# Bendy1.net
KiCad netlist of a schematic drawn in EAGLE
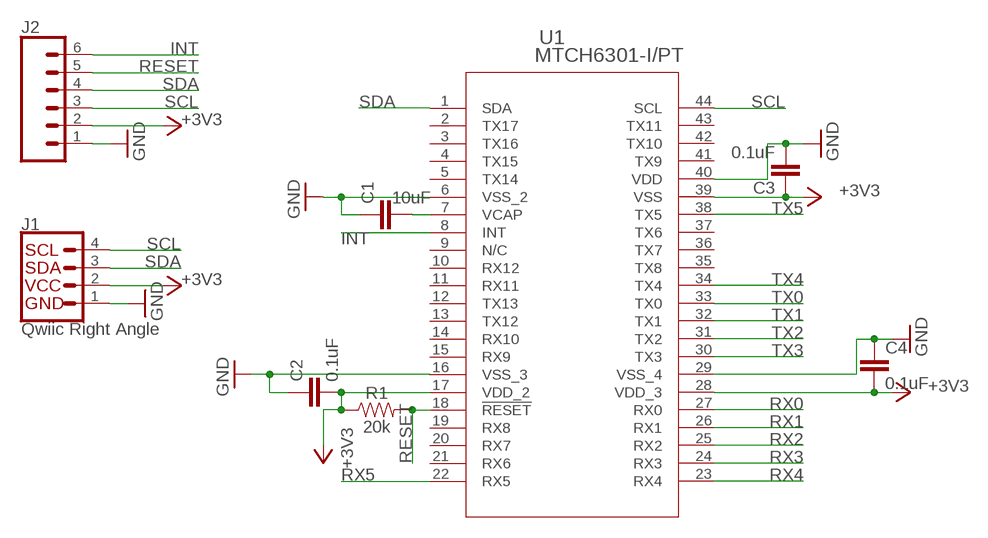
[diagram p0: schematic, sheet 1]

(export (version "E")
  (design (tool "Eeschema 10.0.6"))
  (components
    (comp (ref "C1")
      (value "10uF")
      (footprint "eagle-import:0603")
      (libsource (lib "eagle-import") (part "10UF-0603-6.3V-20%"))
    )
    (comp (ref "C2")
      (value "0.1uF")
      (footprint "eagle-import:0603")
      (libsource (lib "eagle-import") (part "0.1UF-0603-25V-(+80/-20%)"))
    )
    (comp (ref "C3")
      (value "0.1uF")
      (footprint "eagle-import:0603")
      (libsource (lib "eagle-import") (part "0.1UF-0603-25V-(+80/-20%)"))
    )
    (comp (ref "C4")
      (value "0.1uF")
      (footprint "eagle-import:0402")
      (libsource (lib "eagle-import") (part "0.1UF-0402-10V-10%-X7R"))
    )
    (comp (ref "J1")
      (value "Qwiic Right Angle")
      (footprint "eagle-import:JST04_1MM_RA")
      (libsource (lib "eagle-import") (part "I2C_STANDARDQWIIC"))
    )
    (comp (ref "J2")
      (value "CONN_06NO_SILK_FEMALE_PTH")
      (footprint "eagle-import:1X06_NO_SILK")
      (libsource (lib "eagle-import") (part "CONN_06NO_SILK_FEMALE_PTH"))
    )
    (comp (ref "R1")
      (value "20k")
      (footprint "eagle-import:0603")
      (libsource (lib "eagle-import") (part "20KOHM-0603-1/10W-1%"))
    )
    (comp (ref "U1")
      (value "MTCH6301-I/PT")
      (footprint "eagle-import:TQFP44_10X10MC_MCH")
      (fields (field (name "COPYRIGHT") "Copyright (C) 2024 Ultra Librarian. All rights reserved."))
      (libsource (lib "eagle-import") (part "MTCH6301-I/PT"))
    )
  )
  (nets
    (net (code "1") (name "+3V3") (class "Default")
      (node (ref "C2") (pin "2") (pinfunction "2_2") (pintype "passive"))
      (node (ref "C3") (pin "1") (pinfunction "1_1") (pintype "passive"))
      (node (ref "C4") (pin "2") (pinfunction "2_2") (pintype "passive"))
      (node (ref "J1") (pin "2") (pinfunction "2_2") (pintype "power_in"))
      (node (ref "J2") (pin "2") (pinfunction "2_2") (pintype "passive"))
      (node (ref "R1") (pin "1") (pinfunction "1_1") (pintype "passive"))
      (node (ref "U1") (pin "17") (pinfunction "VDD_2_17") (pintype "power_in"))
      (node (ref "U1") (pin "28") (pinfunction "VDD_3_28") (pintype "power_in"))
      (node (ref "U1") (pin "39") (pinfunction "VSS_39") (pintype "passive"))
    )
    (net (code "2") (name "/INT") (class "Default")
      (node (ref "J2") (pin "6") (pinfunction "6_6") (pintype "passive"))
      (node (ref "U1") (pin "8") (pinfunction "INT_8") (pintype "output"))
    )
    (net (code "3") (name "/RESET") (class "Default")
      (node (ref "J2") (pin "5") (pinfunction "5_5") (pintype "passive"))
      (node (ref "R1") (pin "2") (pinfunction "2_2") (pintype "passive"))
      (node (ref "U1") (pin "18") (pinfunction "~{RESET}_18") (pintype "input"))
    )
    (net (code "4") (name "/RX0") (class "Default")
      (node (ref "U1") (pin "27") (pinfunction "RX0_27") (pintype "bidirectional"))
    )
    (net (code "5") (name "/RX1") (class "Default")
      (node (ref "U1") (pin "26") (pinfunction "RX1_26") (pintype "bidirectional"))
    )
    (net (code "6") (name "/RX2") (class "Default")
      (node (ref "U1") (pin "25") (pinfunction "RX2_25") (pintype "bidirectional"))
    )
    (net (code "7") (name "/RX3") (class "Default")
      (node (ref "U1") (pin "24") (pinfunction "RX3_24") (pintype "bidirectional"))
    )
    (net (code "8") (name "/RX4") (class "Default")
      (node (ref "U1") (pin "23") (pinfunction "RX4_23") (pintype "bidirectional"))
    )
    (net (code "9") (name "/RX5") (class "Default")
      (node (ref "U1") (pin "22") (pinfunction "RX5_22") (pintype "bidirectional"))
    )
    (net (code "10") (name "/SCL") (class "Default")
      (node (ref "J1") (pin "4") (pinfunction "4_4") (pintype "passive"))
      (node (ref "J2") (pin "3") (pinfunction "3_3") (pintype "passive"))
      (node (ref "U1") (pin "44") (pinfunction "SCL_44") (pintype "input"))
    )
    (net (code "11") (name "/SDA") (class "Default")
      (node (ref "J1") (pin "3") (pinfunction "3_3") (pintype "passive"))
      (node (ref "J2") (pin "4") (pinfunction "4_4") (pintype "passive"))
      (node (ref "U1") (pin "1") (pinfunction "SDA_1") (pintype "bidirectional"))
    )
    (net (code "12") (name "/TX0") (class "Default")
      (node (ref "U1") (pin "33") (pinfunction "TX0_33") (pintype "bidirectional"))
    )
    (net (code "13") (name "/TX1") (class "Default")
      (node (ref "U1") (pin "32") (pinfunction "TX1_32") (pintype "bidirectional"))
    )
    (net (code "14") (name "/TX2") (class "Default")
      (node (ref "U1") (pin "31") (pinfunction "TX2_31") (pintype "bidirectional"))
    )
    (net (code "15") (name "/TX3") (class "Default")
      (node (ref "U1") (pin "30") (pinfunction "TX3_30") (pintype "bidirectional"))
    )
    (net (code "16") (name "/TX4") (class "Default")
      (node (ref "U1") (pin "34") (pinfunction "TX4_34") (pintype "bidirectional"))
    )
    (net (code "17") (name "/TX5") (class "Default")
      (node (ref "U1") (pin "38") (pinfunction "TX5_38") (pintype "bidirectional"))
    )
    (net (code "18") (name "GND") (class "Default")
      (node (ref "C1") (pin "1") (pinfunction "1_1") (pintype "passive"))
      (node (ref "C2") (pin "1") (pinfunction "1_1") (pintype "passive"))
      (node (ref "C3") (pin "2") (pinfunction "2_2") (pintype "passive"))
      (node (ref "C4") (pin "1") (pinfunction "1_1") (pintype "passive"))
      (node (ref "J1") (pin "1") (pinfunction "1_1") (pintype "power_in"))
      (node (ref "J2") (pin "1") (pinfunction "1_1") (pintype "passive"))
      (node (ref "U1") (pin "16") (pinfunction "VSS_3_16") (pintype "passive"))
      (node (ref "U1") (pin "29") (pinfunction "VSS_4_29") (pintype "passive"))
      (node (ref "U1") (pin "40") (pinfunction "VDD_40") (pintype "power_in"))
      (node (ref "U1") (pin "6") (pinfunction "VSS_2_6") (pintype "power_in"))
    )
    (net (code "19") (name "Net-(U1-VCAP)") (class "Default")
      (node (ref "C1") (pin "2") (pinfunction "2_2") (pintype "passive"))
      (node (ref "U1") (pin "7") (pinfunction "VCAP_7") (pintype "power_in"))
    )
    (net (code "20") (name "unconnected-(U1-N{slash}C-Pad9)") (class "Default")
      (node (ref "U1") (pin "9") (pinfunction "N/C_9") (pintype "no_connect"))
    )
    (net (code "21") (name "unconnected-(U1-RX6-Pad21)") (class "Default")
      (node (ref "U1") (pin "21") (pinfunction "RX6_21") (pintype "bidirectional"))
    )
    (net (code "22") (name "unconnected-(U1-RX7-Pad20)") (class "Default")
      (node (ref "U1") (pin "20") (pinfunction "RX7_20") (pintype "bidirectional"))
    )
    (net (code "23") (name "unconnected-(U1-RX8-Pad19)") (class "Default")
      (node (ref "U1") (pin "19") (pinfunction "RX8_19") (pintype "bidirectional"))
    )
    (net (code "24") (name "unconnected-(U1-RX9-Pad15)") (class "Default")
      (node (ref "U1") (pin "15") (pinfunction "RX9_15") (pintype "bidirectional"))
    )
    (net (code "25") (name "unconnected-(U1-RX10-Pad14)") (class "Default")
      (node (ref "U1") (pin "14") (pinfunction "RX10_14") (pintype "bidirectional"))
    )
    (net (code "26") (name "unconnected-(U1-RX11-Pad11)") (class "Default")
      (node (ref "U1") (pin "11") (pinfunction "RX11_11") (pintype "bidirectional"))
    )
    (net (code "27") (name "unconnected-(U1-RX12-Pad10)") (class "Default")
      (node (ref "U1") (pin "10") (pinfunction "RX12_10") (pintype "bidirectional"))
    )
    (net (code "28") (name "unconnected-(U1-TX6-Pad37)") (class "Default")
      (node (ref "U1") (pin "37") (pinfunction "TX6_37") (pintype "bidirectional"))
    )
    (net (code "29") (name "unconnected-(U1-TX7-Pad36)") (class "Default")
      (node (ref "U1") (pin "36") (pinfunction "TX7_36") (pintype "bidirectional"))
    )
    (net (code "30") (name "unconnected-(U1-TX8-Pad35)") (class "Default")
      (node (ref "U1") (pin "35") (pinfunction "TX8_35") (pintype "bidirectional"))
    )
    (net (code "31") (name "unconnected-(U1-TX9-Pad41)") (class "Default")
      (node (ref "U1") (pin "41") (pinfunction "TX9_41") (pintype "bidirectional"))
    )
    (net (code "32") (name "unconnected-(U1-TX10-Pad42)") (class "Default")
      (node (ref "U1") (pin "42") (pinfunction "TX10_42") (pintype "bidirectional"))
    )
    (net (code "33") (name "unconnected-(U1-TX11-Pad43)") (class "Default")
      (node (ref "U1") (pin "43") (pinfunction "TX11_43") (pintype "bidirectional"))
    )
    (net (code "34") (name "unconnected-(U1-TX12-Pad13)") (class "Default")
      (node (ref "U1") (pin "13") (pinfunction "TX12_13") (pintype "bidirectional"))
    )
    (net (code "35") (name "unconnected-(U1-TX13-Pad12)") (class "Default")
      (node (ref "U1") (pin "12") (pinfunction "TX13_12") (pintype "bidirectional"))
    )
    (net (code "36") (name "unconnected-(U1-TX14-Pad5)") (class "Default")
      (node (ref "U1") (pin "5") (pinfunction "TX14_5") (pintype "bidirectional"))
    )
    (net (code "37") (name "unconnected-(U1-TX15-Pad4)") (class "Default")
      (node (ref "U1") (pin "4") (pinfunction "TX15_4") (pintype "bidirectional"))
    )
    (net (code "38") (name "unconnected-(U1-TX16-Pad3)") (class "Default")
      (node (ref "U1") (pin "3") (pinfunction "TX16_3") (pintype "bidirectional"))
    )
    (net (code "39") (name "unconnected-(U1-TX17-Pad2)") (class "Default")
      (node (ref "U1") (pin "2") (pinfunction "TX17_2") (pintype "bidirectional"))
    )
  )
)
